# main.net
KiCad netlist of a schematic drawn in Altium Designer
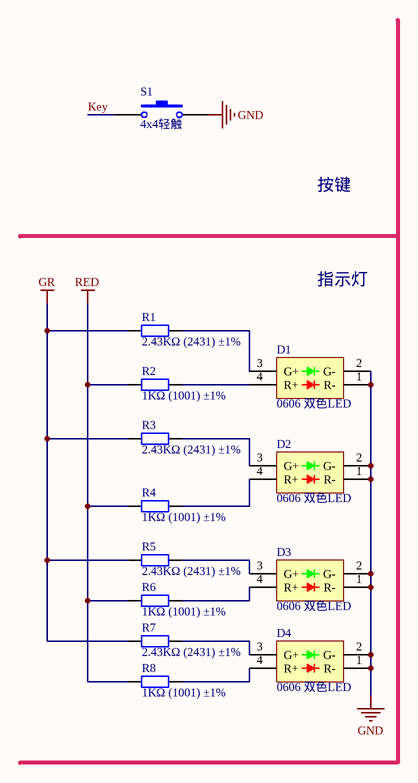
[diagram p0: main.SchDoc]

(export (version "E")
  (design (tool "Eeschema 10.0.6"))
  (components
    (comp (ref "D1")
      (value "0606 双色LED")
      (footprint "LED-SMD_4P-L1.6-W1.5-TL-1")
      (description "0606 双色LED 红色/翠绿")
      (libsource (lib "custom") (part "0606DualColor LED"))
    )
    (comp (ref "D2")
      (value "0606 双色LED")
      (footprint "LED-SMD_4P-L1.6-W1.5-TL-1")
      (description "0606 双色LED 红色/翠绿")
      (libsource (lib "custom") (part "0606DualColor LED"))
    )
    (comp (ref "D3")
      (value "0606 双色LED")
      (footprint "LED-SMD_4P-L1.6-W1.5-TL-1")
      (description "0606 双色LED 红色/翠绿")
      (libsource (lib "custom") (part "0606DualColor LED"))
    )
    (comp (ref "D4")
      (value "0606 双色LED")
      (footprint "LED-SMD_4P-L1.6-W1.5-TL-1")
      (description "0606 双色LED 红色/翠绿")
      (libsource (lib "custom") (part "0606DualColor LED"))
    )
    (comp (ref "R1")
      (value "2.43KΩ (2431) ±1%")
      (footprint "0402_R")
      (description "贴片电阻")
      (libsource (lib "Miscellaneous Devices LC") (part "0402 2KΩ (2001) 1%"))
    )
    (comp (ref "R2")
      (value "1KΩ (1001) ±1%")
      (footprint "0402_R")
      (description "贴片电阻")
      (libsource (lib "Miscellaneous Devices LC") (part "0402 1KΩ (1001) 1%"))
    )
    (comp (ref "R3")
      (value "2.43KΩ (2431) ±1%")
      (footprint "0402_R")
      (description "贴片电阻")
      (libsource (lib "Miscellaneous Devices LC") (part "0402 2KΩ (2001) 1%"))
    )
    (comp (ref "R4")
      (value "1KΩ (1001) ±1%")
      (footprint "0402_R")
      (description "贴片电阻")
      (libsource (lib "Miscellaneous Devices LC") (part "0402 1KΩ (1001) 1%"))
    )
    (comp (ref "R5")
      (value "2.43KΩ (2431) ±1%")
      (footprint "0402_R")
      (description "贴片电阻")
      (libsource (lib "Miscellaneous Devices LC") (part "0402 2KΩ (2001) 1%"))
    )
    (comp (ref "R6")
      (value "1KΩ (1001) ±1%")
      (footprint "0402_R")
      (description "贴片电阻")
      (libsource (lib "Miscellaneous Devices LC") (part "0402 1KΩ (1001) 1%"))
    )
    (comp (ref "R7")
      (value "2.43KΩ (2431) ±1%")
      (footprint "0402_R")
      (description "贴片电阻")
      (libsource (lib "Miscellaneous Devices LC") (part "0402 2KΩ (2001) 1%"))
    )
    (comp (ref "R8")
      (value "1KΩ (1001) ±1%")
      (footprint "0402_R")
      (description "贴片电阻")
      (libsource (lib "Miscellaneous Devices LC") (part "0402 1KΩ (1001) 1%"))
    )
    (comp (ref "S1")
      (value "4x4轻触")
      (footprint "SW-SMD_4P-L5.2-W5.2-P3.70-LS6.4")
      (description "Switch")
      (fields (field (name "PUBLISHER") "Altium Limited"))
      (libsource (lib "Miscellaneous Devices") (part "SW-PB"))
    )
  )
  (nets
    (net (code "1") (name "/Key") (class "Default")
      (node (ref "S1") (pin "1") (pinfunction "1_1") (pintype "passive"))
    )
    (net (code "2") (name "GND") (class "Default")
      (node (ref "D1") (pin "1") (pinfunction "R-_1") (pintype "passive"))
      (node (ref "D1") (pin "2") (pinfunction "G-_2") (pintype "passive"))
      (node (ref "D2") (pin "1") (pinfunction "R-_1") (pintype "passive"))
      (node (ref "D2") (pin "2") (pinfunction "G-_2") (pintype "passive"))
      (node (ref "D3") (pin "1") (pinfunction "R-_1") (pintype "passive"))
      (node (ref "D3") (pin "2") (pinfunction "G-_2") (pintype "passive"))
      (node (ref "D4") (pin "1") (pinfunction "R-_1") (pintype "passive"))
      (node (ref "D4") (pin "2") (pinfunction "G-_2") (pintype "passive"))
      (node (ref "S1") (pin "2") (pinfunction "2_2") (pintype "passive"))
    )
    (net (code "3") (name "GR") (class "Default")
      (node (ref "R1") (pin "1") (pinfunction "1_1") (pintype "passive"))
      (node (ref "R3") (pin "1") (pinfunction "1_1") (pintype "passive"))
      (node (ref "R5") (pin "1") (pinfunction "1_1") (pintype "passive"))
      (node (ref "R7") (pin "1") (pinfunction "1_1") (pintype "passive"))
    )
    (net (code "4") (name "Net-(D1-G+)") (class "Default")
      (node (ref "D1") (pin "3") (pinfunction "G+_3") (pintype "passive"))
      (node (ref "R1") (pin "2") (pinfunction "2_2") (pintype "passive"))
    )
    (net (code "5") (name "Net-(D1-R+)") (class "Default")
      (node (ref "D1") (pin "4") (pinfunction "R+_4") (pintype "passive"))
      (node (ref "R2") (pin "2") (pinfunction "2_2") (pintype "passive"))
    )
    (net (code "6") (name "Net-(D2-G+)") (class "Default")
      (node (ref "D2") (pin "3") (pinfunction "G+_3") (pintype "passive"))
      (node (ref "R3") (pin "2") (pinfunction "2_2") (pintype "passive"))
    )
    (net (code "7") (name "Net-(D2-R+)") (class "Default")
      (node (ref "D2") (pin "4") (pinfunction "R+_4") (pintype "passive"))
      (node (ref "R4") (pin "2") (pinfunction "2_2") (pintype "passive"))
    )
    (net (code "8") (name "Net-(D3-G+)") (class "Default")
      (node (ref "D3") (pin "3") (pinfunction "G+_3") (pintype "passive"))
      (node (ref "R5") (pin "2") (pinfunction "2_2") (pintype "passive"))
    )
    (net (code "9") (name "Net-(D3-R+)") (class "Default")
      (node (ref "D3") (pin "4") (pinfunction "R+_4") (pintype "passive"))
      (node (ref "R6") (pin "2") (pinfunction "2_2") (pintype "passive"))
    )
    (net (code "10") (name "Net-(D4-G+)") (class "Default")
      (node (ref "D4") (pin "3") (pinfunction "G+_3") (pintype "passive"))
      (node (ref "R7") (pin "2") (pinfunction "2_2") (pintype "passive"))
    )
    (net (code "11") (name "Net-(D4-R+)") (class "Default")
      (node (ref "D4") (pin "4") (pinfunction "R+_4") (pintype "passive"))
      (node (ref "R8") (pin "2") (pinfunction "2_2") (pintype "passive"))
    )
    (net (code "12") (name "RED") (class "Default")
      (node (ref "R2") (pin "1") (pinfunction "1_1") (pintype "passive"))
      (node (ref "R4") (pin "1") (pinfunction "1_1") (pintype "passive"))
      (node (ref "R6") (pin "1") (pinfunction "1_1") (pintype "passive"))
      (node (ref "R8") (pin "1") (pinfunction "1_1") (pintype "passive"))
    )
  )
)
